# T6.net
KiCad netlist of a schematic drawn in Altium Designer
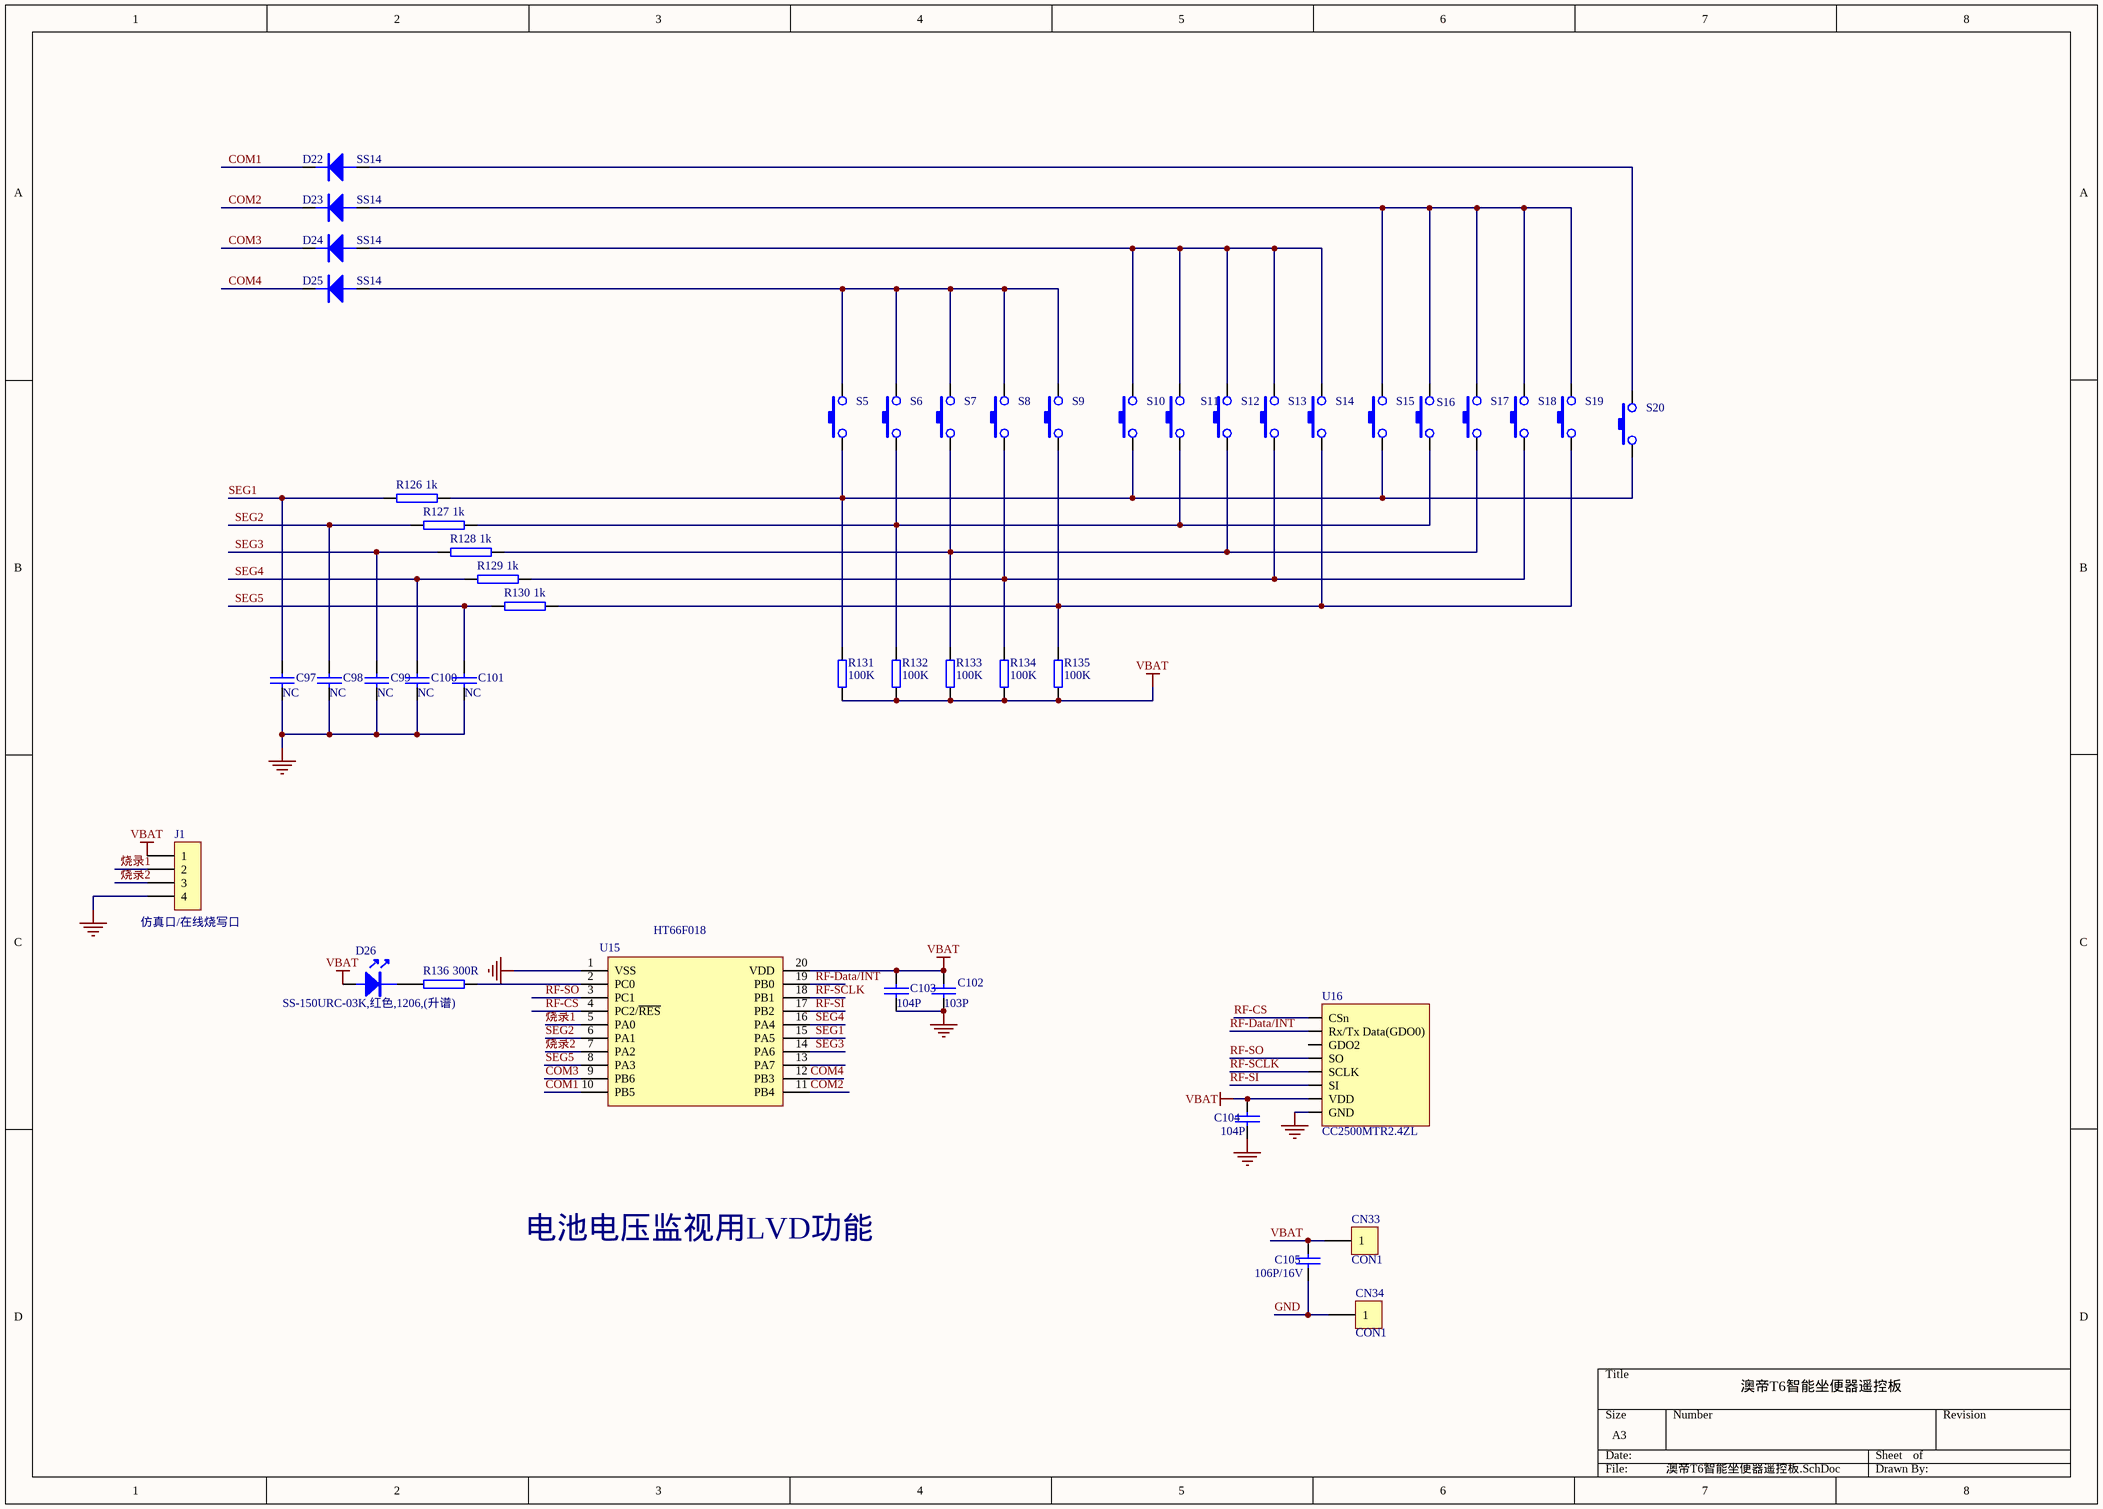
[diagram p0: 澳帝T6智能坐便器遥控板.SchDoc]

(export (version "E")
  (design (tool "Eeschema 10.0.6"))
  (components
    (comp (ref "C97")
      (value "NC")
      (footprint "C0805-T")
      (description "Capacitor")
      (libsource (lib "*") (part "CAP"))
    )
    (comp (ref "C98")
      (value "NC")
      (footprint "C0805-T")
      (description "Capacitor")
      (libsource (lib "*") (part "CAP"))
    )
    (comp (ref "C99")
      (value "NC")
      (footprint "C0805-T")
      (description "Capacitor")
      (libsource (lib "*") (part "CAP"))
    )
    (comp (ref "C100")
      (value "NC")
      (footprint "C0805-T")
      (description "Capacitor")
      (libsource (lib "*") (part "CAP"))
    )
    (comp (ref "C101")
      (value "NC")
      (footprint "C0805-T")
      (description "Capacitor")
      (libsource (lib "*") (part "CAP"))
    )
    (comp (ref "C102")
      (value "103P")
      (footprint "C0805-T")
      (description "Capacitor")
      (libsource (lib "*") (part "CAP"))
    )
    (comp (ref "C103")
      (value "104P")
      (footprint "C0805-T")
      (description "Capacitor")
      (libsource (lib "*") (part "CAP"))
    )
    (comp (ref "C104")
      (value "104P")
      (footprint "C0805-T")
      (description "Capacitor")
      (libsource (lib "*") (part "CAP"))
    )
    (comp (ref "C105")
      (value "106P/16V")
      (footprint "C0805-T")
      (description "Capacitor")
      (libsource (lib "*") (part "CAP"))
    )
    (comp (ref "CN33")
      (value "CON1")
      (footprint "_TESTPIONT")
      (description "Connector")
      (libsource (lib "*") (part "CON1"))
    )
    (comp (ref "CN34")
      (value "CON1")
      (footprint "_TESTPIONT")
      (description "Connector")
      (libsource (lib "*") (part "CON1"))
    )
    (comp (ref "D22")
      (value "SS14")
      (footprint "D-SMA-T")
      (description "Diode")
      (libsource (lib "*") (part "DIODE"))
    )
    (comp (ref "D23")
      (value "SS14")
      (footprint "D-SMA-T")
      (description "Diode")
      (libsource (lib "*") (part "DIODE"))
    )
    (comp (ref "D24")
      (value "SS14")
      (footprint "D-SMA-T")
      (description "Diode")
      (libsource (lib "*") (part "DIODE"))
    )
    (comp (ref "D25")
      (value "SS14")
      (footprint "D-SMA-T")
      (description "Diode")
      (libsource (lib "*") (part "DIODE"))
    )
    (comp (ref "D26")
      (value "SS-150URC-03K,红色,1206,(升谱)")
      (footprint "LED-1206-T")
      (libsource (lib "*") (part "LED"))
    )
    (comp (ref "J1")
      (value "仿真口/在线烧写口")
      (footprint "PZ-1*4-M-SI")
      (description "Connector")
      (libsource (lib "*") (part "CON4"))
    )
    (comp (ref "R126") (value "1k") (footprint "R0805-T") (libsource (lib "") (part "RES2_1")))
    (comp (ref "R127") (value "1k") (footprint "R0805-T") (libsource (lib "") (part "RES2_1")))
    (comp (ref "R128") (value "1k") (footprint "R0805-T") (libsource (lib "") (part "RES2_1")))
    (comp (ref "R129") (value "1k") (footprint "R0805-T") (libsource (lib "") (part "RES2_1")))
    (comp (ref "R130") (value "1k") (footprint "R0805-T") (libsource (lib "") (part "RES2_1")))
    (comp (ref "R131") (value "100K") (footprint "R0805-T") (libsource (lib "*") (part "RES2")))
    (comp (ref "R132") (value "100K") (footprint "R0805-T") (libsource (lib "*") (part "RES2")))
    (comp (ref "R133") (value "100K") (footprint "R0805-T") (libsource (lib "*") (part "RES2")))
    (comp (ref "R134") (value "100K") (footprint "R0805-T") (libsource (lib "*") (part "RES2")))
    (comp (ref "R135") (value "100K") (footprint "R0805-T") (libsource (lib "*") (part "RES2")))
    (comp (ref "R136") (value "300R") (footprint "R0805-T") (libsource (lib "") (part "RES2_1")))
    (comp (ref "S5") (value "水压、暖风-") (footprint "KG6*6") (libsource (lib "*") (part "SW-PB")))
    (comp (ref "S6") (value "6*6*5") (footprint "KG6*6") (libsource (lib "*") (part "SW-PB")))
    (comp (ref "S7") (value "座温调节") (footprint "KG6*6") (libsource (lib "*") (part "SW-PB")))
    (comp (ref "S8") (value "座温调节") (footprint "KG6*6") (libsource (lib "*") (part "SW-PB")))
    (comp (ref "S9") (value "座温调节") (footprint "KG6*6") (libsource (lib "*") (part "SW-PB")))
    (comp (ref "S10") (value "座温调节") (footprint "KG6*6") (libsource (lib "*") (part "SW-PB")))
    (comp (ref "S11") (value "座温调节") (footprint "KG6*6") (libsource (lib "*") (part "SW-PB")))
    (comp (ref "S12") (value "座温调节") (footprint "KG6*6") (libsource (lib "*") (part "SW-PB")))
    (comp (ref "S13") (value "座温调节") (footprint "KG6*6") (libsource (lib "*") (part "SW-PB")))
    (comp (ref "S14") (value "座温调节") (footprint "KG6*6") (libsource (lib "*") (part "SW-PB")))
    (comp (ref "S15") (value "座温调节") (footprint "KG6*6") (libsource (lib "*") (part "SW-PB")))
    (comp (ref "S16") (value "座温调节") (footprint "KG6*6") (libsource (lib "*") (part "SW-PB")))
    (comp (ref "S17") (value "座温调节") (footprint "KG6*6") (libsource (lib "*") (part "SW-PB")))
    (comp (ref "S18") (value "座温调节") (footprint "KG6*6") (libsource (lib "*") (part "SW-PB")))
    (comp (ref "S19") (value "座温调节") (footprint "KG6*6") (libsource (lib "*") (part "SW-PB")))
    (comp (ref "S20") (value "座温调节") (footprint "KG6*6") (libsource (lib "*") (part "SW-PB")))
    (comp (ref "U15") (value "HT66F018") (footprint "SOP20-7.6-1.27") (libsource (lib "*") (part "HT66F004")))
    (comp (ref "U16")
      (value "CC2500MTR2.4ZL")
      (footprint "CC2500MTR2.4ZL")
      (libsource (lib "*") (part "2.4GRF"))
    )
  )
  (nets
    (net (code "1") (name "/COM1") (class "Default")
      (node (ref "D22") (pin "K") (pinfunction "K_K") (pintype "passive"))
      (node (ref "U15") (pin "10") (pinfunction "PB5_10") (pintype "passive"))
    )
    (net (code "2") (name "/COM2") (class "Default")
      (node (ref "D23") (pin "K") (pinfunction "K_K") (pintype "passive"))
      (node (ref "U15") (pin "11") (pinfunction "PB4_11") (pintype "passive"))
    )
    (net (code "3") (name "/COM3") (class "Default")
      (node (ref "D24") (pin "K") (pinfunction "K_K") (pintype "passive"))
      (node (ref "U15") (pin "9") (pinfunction "PB6_9") (pintype "passive"))
    )
    (net (code "4") (name "/COM4") (class "Default")
      (node (ref "D25") (pin "K") (pinfunction "K_K") (pintype "passive"))
      (node (ref "U15") (pin "12") (pinfunction "PB3_12") (pintype "passive"))
    )
    (net (code "5") (name "/RF-CS") (class "Default")
      (node (ref "U15") (pin "4") (pinfunction "PC2/~{RES}_4") (pintype "passive"))
      (node (ref "U16") (pin "8") (pinfunction "CSn_8") (pintype "passive"))
    )
    (net (code "6") (name "/RF-Data{slash}INT") (class "Default")
      (node (ref "U15") (pin "19") (pinfunction "PB0_19") (pintype "passive"))
      (node (ref "U16") (pin "7") (pinfunction "Rx/Tx_Data(GDO0)_7") (pintype "passive"))
    )
    (net (code "7") (name "/RF-SCLK") (class "Default")
      (node (ref "U15") (pin "18") (pinfunction "PB1_18") (pintype "passive"))
      (node (ref "U16") (pin "4") (pinfunction "SCLK_4") (pintype "passive"))
    )
    (net (code "8") (name "/RF-SI") (class "Default")
      (node (ref "U15") (pin "17") (pinfunction "PB2_17") (pintype "passive"))
      (node (ref "U16") (pin "3") (pinfunction "SI_3") (pintype "passive"))
    )
    (net (code "9") (name "/RF-SO") (class "Default")
      (node (ref "U15") (pin "3") (pinfunction "PC1_3") (pintype "passive"))
      (node (ref "U16") (pin "5") (pinfunction "SO_5") (pintype "passive"))
    )
    (net (code "10") (name "/SEG1") (class "Default")
      (node (ref "C97") (pin "1") (pinfunction "1_1") (pintype "passive"))
      (node (ref "R126") (pin "1") (pinfunction "1_1") (pintype "passive"))
      (node (ref "U15") (pin "15") (pinfunction "PA5_15") (pintype "passive"))
    )
    (net (code "11") (name "/SEG2") (class "Default")
      (node (ref "C98") (pin "1") (pinfunction "1_1") (pintype "passive"))
      (node (ref "R127") (pin "1") (pinfunction "1_1") (pintype "passive"))
      (node (ref "U15") (pin "6") (pinfunction "PA1_6") (pintype "passive"))
    )
    (net (code "12") (name "/SEG3") (class "Default")
      (node (ref "C99") (pin "1") (pinfunction "1_1") (pintype "passive"))
      (node (ref "R128") (pin "1") (pinfunction "1_1") (pintype "passive"))
      (node (ref "U15") (pin "14") (pinfunction "PA6_14") (pintype "passive"))
    )
    (net (code "13") (name "/SEG4") (class "Default")
      (node (ref "C100") (pin "1") (pinfunction "1_1") (pintype "passive"))
      (node (ref "R129") (pin "1") (pinfunction "1_1") (pintype "passive"))
      (node (ref "U15") (pin "16") (pinfunction "PA4_16") (pintype "passive"))
    )
    (net (code "14") (name "/SEG5") (class "Default")
      (node (ref "C101") (pin "1") (pinfunction "1_1") (pintype "passive"))
      (node (ref "R130") (pin "1") (pinfunction "1_1") (pintype "passive"))
      (node (ref "U15") (pin "8") (pinfunction "PA3_8") (pintype "passive"))
    )
    (net (code "15") (name "/烧录1") (class "Default")
      (node (ref "J1") (pin "2") (pinfunction "2_2") (pintype "passive"))
      (node (ref "U15") (pin "5") (pinfunction "PA0_5") (pintype "passive"))
    )
    (net (code "16") (name "/烧录2") (class "Default")
      (node (ref "J1") (pin "3") (pinfunction "3_3") (pintype "passive"))
      (node (ref "U15") (pin "7") (pinfunction "PA2_7") (pintype "passive"))
    )
    (net (code "17") (name "GND") (class "Default")
      (node (ref "C100") (pin "2") (pinfunction "2_2") (pintype "passive"))
      (node (ref "C101") (pin "2") (pinfunction "2_2") (pintype "passive"))
      (node (ref "C102") (pin "2") (pinfunction "2_2") (pintype "passive"))
      (node (ref "C103") (pin "2") (pinfunction "2_2") (pintype "passive"))
      (node (ref "C104") (pin "2") (pinfunction "2_2") (pintype "passive"))
      (node (ref "C105") (pin "2") (pinfunction "2_2") (pintype "passive"))
      (node (ref "C97") (pin "2") (pinfunction "2_2") (pintype "passive"))
      (node (ref "C98") (pin "2") (pinfunction "2_2") (pintype "passive"))
      (node (ref "C99") (pin "2") (pinfunction "2_2") (pintype "passive"))
      (node (ref "CN34") (pin "1") (pinfunction "1_1") (pintype "passive"))
      (node (ref "J1") (pin "4") (pinfunction "4_4") (pintype "passive"))
      (node (ref "U15") (pin "1") (pinfunction "VSS_1") (pintype "passive"))
      (node (ref "U16") (pin "1") (pinfunction "GND_1") (pintype "passive"))
    )
    (net (code "18") (name "Net-(D22-PadA)") (class "Default")
      (node (ref "D22") (pin "A") (pinfunction "A_A") (pintype "passive"))
      (node (ref "S20") (pin "2") (pinfunction "2_2") (pintype "passive"))
    )
    (net (code "19") (name "Net-(D23-PadA)") (class "Default")
      (node (ref "D23") (pin "A") (pinfunction "A_A") (pintype "passive"))
      (node (ref "S15") (pin "2") (pinfunction "2_2") (pintype "passive"))
      (node (ref "S16") (pin "2") (pinfunction "2_2") (pintype "passive"))
      (node (ref "S17") (pin "2") (pinfunction "2_2") (pintype "passive"))
      (node (ref "S18") (pin "2") (pinfunction "2_2") (pintype "passive"))
      (node (ref "S19") (pin "2") (pinfunction "2_2") (pintype "passive"))
    )
    (net (code "20") (name "Net-(D24-PadA)") (class "Default")
      (node (ref "D24") (pin "A") (pinfunction "A_A") (pintype "passive"))
      (node (ref "S10") (pin "2") (pinfunction "2_2") (pintype "passive"))
      (node (ref "S11") (pin "2") (pinfunction "2_2") (pintype "passive"))
      (node (ref "S12") (pin "2") (pinfunction "2_2") (pintype "passive"))
      (node (ref "S13") (pin "2") (pinfunction "2_2") (pintype "passive"))
      (node (ref "S14") (pin "2") (pinfunction "2_2") (pintype "passive"))
    )
    (net (code "21") (name "Net-(D25-PadA)") (class "Default")
      (node (ref "D25") (pin "A") (pinfunction "A_A") (pintype "passive"))
      (node (ref "S5") (pin "2") (pinfunction "2_2") (pintype "passive"))
      (node (ref "S6") (pin "2") (pinfunction "2_2") (pintype "passive"))
      (node (ref "S7") (pin "2") (pinfunction "2_2") (pintype "passive"))
      (node (ref "S8") (pin "2") (pinfunction "2_2") (pintype "passive"))
      (node (ref "S9") (pin "2") (pinfunction "2_2") (pintype "passive"))
    )
    (net (code "22") (name "Net-(D26-2)") (class "Default")
      (node (ref "D26") (pin "K") (pinfunction "2_K") (pintype "passive"))
      (node (ref "R136") (pin "1") (pinfunction "1_1") (pintype "passive"))
    )
    (net (code "23") (name "Net-(R126-Pad2)") (class "Default")
      (node (ref "R126") (pin "2") (pinfunction "2_2") (pintype "passive"))
      (node (ref "R131") (pin "1") (pinfunction "1_1") (pintype "passive"))
      (node (ref "S10") (pin "1") (pinfunction "1_1") (pintype "passive"))
      (node (ref "S15") (pin "1") (pinfunction "1_1") (pintype "passive"))
      (node (ref "S20") (pin "1") (pinfunction "1_1") (pintype "passive"))
      (node (ref "S5") (pin "1") (pinfunction "1_1") (pintype "passive"))
    )
    (net (code "24") (name "Net-(R127-Pad2)") (class "Default")
      (node (ref "R127") (pin "2") (pinfunction "2_2") (pintype "passive"))
      (node (ref "R132") (pin "1") (pinfunction "1_1") (pintype "passive"))
      (node (ref "S11") (pin "1") (pinfunction "1_1") (pintype "passive"))
      (node (ref "S16") (pin "1") (pinfunction "1_1") (pintype "passive"))
      (node (ref "S6") (pin "1") (pinfunction "1_1") (pintype "passive"))
    )
    (net (code "25") (name "Net-(R128-Pad2)") (class "Default")
      (node (ref "R128") (pin "2") (pinfunction "2_2") (pintype "passive"))
      (node (ref "R133") (pin "1") (pinfunction "1_1") (pintype "passive"))
      (node (ref "S12") (pin "1") (pinfunction "1_1") (pintype "passive"))
      (node (ref "S17") (pin "1") (pinfunction "1_1") (pintype "passive"))
      (node (ref "S7") (pin "1") (pinfunction "1_1") (pintype "passive"))
    )
    (net (code "26") (name "Net-(R129-Pad2)") (class "Default")
      (node (ref "R129") (pin "2") (pinfunction "2_2") (pintype "passive"))
      (node (ref "R134") (pin "1") (pinfunction "1_1") (pintype "passive"))
      (node (ref "S13") (pin "1") (pinfunction "1_1") (pintype "passive"))
      (node (ref "S18") (pin "1") (pinfunction "1_1") (pintype "passive"))
      (node (ref "S8") (pin "1") (pinfunction "1_1") (pintype "passive"))
    )
    (net (code "27") (name "Net-(R130-Pad2)") (class "Default")
      (node (ref "R130") (pin "2") (pinfunction "2_2") (pintype "passive"))
      (node (ref "R135") (pin "1") (pinfunction "1_1") (pintype "passive"))
      (node (ref "S14") (pin "1") (pinfunction "1_1") (pintype "passive"))
      (node (ref "S19") (pin "1") (pinfunction "1_1") (pintype "passive"))
      (node (ref "S9") (pin "1") (pinfunction "1_1") (pintype "passive"))
    )
    (net (code "28") (name "Net-(U15-PC0)") (class "Default")
      (node (ref "R136") (pin "2") (pinfunction "2_2") (pintype "passive"))
      (node (ref "U15") (pin "2") (pinfunction "PC0_2") (pintype "passive"))
    )
    (net (code "29") (name "VBAT") (class "Default")
      (node (ref "C102") (pin "1") (pinfunction "1_1") (pintype "passive"))
      (node (ref "C103") (pin "1") (pinfunction "1_1") (pintype "passive"))
      (node (ref "C104") (pin "1") (pinfunction "1_1") (pintype "passive"))
      (node (ref "C105") (pin "1") (pinfunction "1_1") (pintype "passive"))
      (node (ref "CN33") (pin "1") (pinfunction "1_1") (pintype "passive"))
      (node (ref "D26") (pin "A") (pinfunction "1_A") (pintype "passive"))
      (node (ref "J1") (pin "1") (pinfunction "1_1") (pintype "passive"))
      (node (ref "R131") (pin "2") (pinfunction "2_2") (pintype "passive"))
      (node (ref "R132") (pin "2") (pinfunction "2_2") (pintype "passive"))
      (node (ref "R133") (pin "2") (pinfunction "2_2") (pintype "passive"))
      (node (ref "R134") (pin "2") (pinfunction "2_2") (pintype "passive"))
      (node (ref "R135") (pin "2") (pinfunction "2_2") (pintype "passive"))
      (node (ref "U15") (pin "20") (pinfunction "VDD_20") (pintype "passive"))
      (node (ref "U16") (pin "2") (pinfunction "VDD_2") (pintype "passive"))
    )
    (net (code "30") (name "unconnected-(U15-PA7-Pad13)") (class "Default")
      (node (ref "U15") (pin "13") (pinfunction "PA7_13") (pintype "passive"))
    )
    (net (code "31") (name "unconnected-(U16-GDO2-Pad6)") (class "Default")
      (node (ref "U16") (pin "6") (pinfunction "GDO2_6") (pintype "passive"))
    )
  )
)
